# delta-bob-cat.net
KiCad netlist of a schematic drawn in Altium Designer
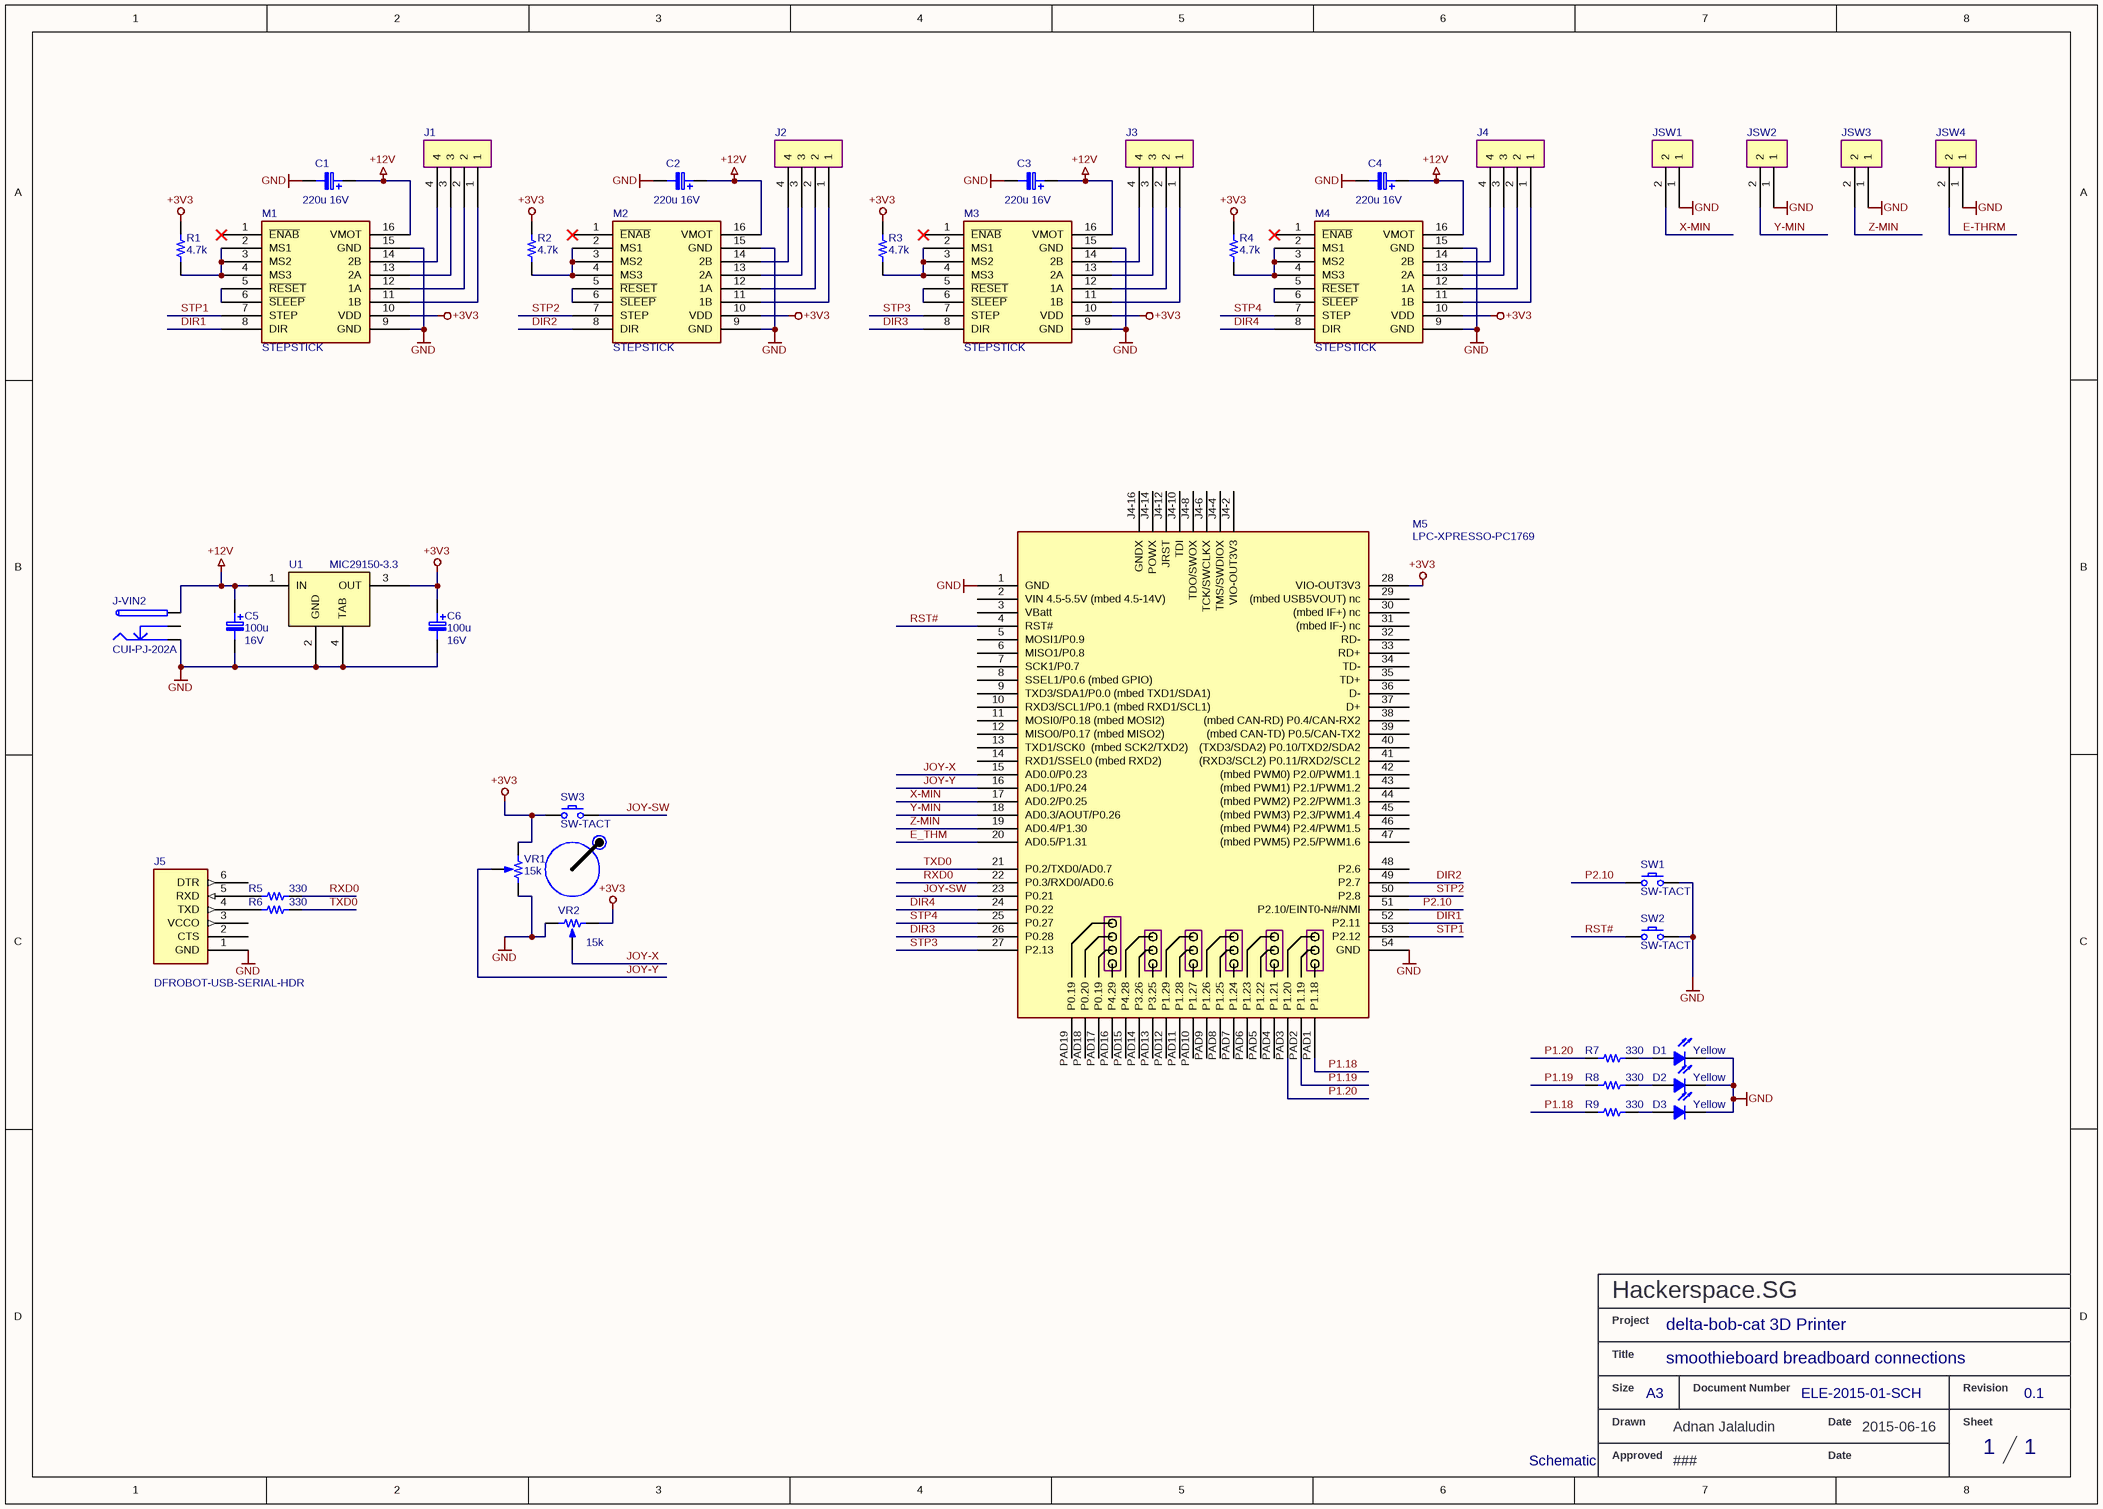
[diagram p0: delta-bob-cat.SchDoc]

(export (version "E")
  (design (tool "Eeschema 10.0.6"))
  (components
    (comp (ref "C1")
      (value "220u")
      (footprint "ECAP-D")
      (description "Cap Elect SMT Dia 6.3mm")
      (fields (field (name "TOLERANCE") "20%") (field (name "RATING") "16V"))
      (libsource (lib "AjDiscrete") (part "CElect"))
    )
    (comp (ref "C2")
      (value "220u")
      (footprint "ECAP-D")
      (description "Cap Elect SMT Dia 6.3mm")
      (fields (field (name "TOLERANCE") "20%") (field (name "RATING") "16V"))
      (libsource (lib "AjDiscrete") (part "CElect"))
    )
    (comp (ref "C3")
      (value "220u")
      (footprint "ECAP-D")
      (description "Cap Elect SMT Dia 6.3mm")
      (fields (field (name "TOLERANCE") "20%") (field (name "RATING") "16V"))
      (libsource (lib "AjDiscrete") (part "CElect"))
    )
    (comp (ref "C4")
      (value "220u")
      (footprint "ECAP-D")
      (description "Cap Elect SMT Dia 6.3mm")
      (fields (field (name "TOLERANCE") "20%") (field (name "RATING") "16V"))
      (libsource (lib "AjDiscrete") (part "CElect"))
    )
    (comp (ref "C5")
      (value "100u")
      (footprint "ECAP-A")
      (description "Cap Elect")
      (fields (field (name "TOLERANCE") "20%") (field (name "RATING") "16V"))
      (libsource (lib "AjDiscrete") (part "CElect"))
    )
    (comp (ref "C6")
      (value "100u")
      (footprint "ECAP-A")
      (description "Cap Elect")
      (fields (field (name "TOLERANCE") "20%") (field (name "RATING") "16V"))
      (libsource (lib "AjDiscrete") (part "CElect"))
    )
    (comp (ref "D1")
      (value "Yellow")
      (footprint "RC0603P")
      (description "LED")
      (libsource (lib "AjDiscrete") (part "LED_OLD"))
    )
    (comp (ref "D2")
      (value "Yellow")
      (footprint "RC0603P")
      (description "LED")
      (libsource (lib "AjDiscrete") (part "LED_OLD"))
    )
    (comp (ref "D3")
      (value "Yellow")
      (footprint "RC0603P")
      (description "LED")
      (libsource (lib "AjDiscrete") (part "LED_OLD"))
    )
    (comp (ref "J-VIN2")
      (value "CUI-PJ-202A")
      (footprint "POWER-CUI-PJ-202A")
      (description "Jack Power 2.10/6.50mm")
      (libsource (lib "AjConn") (part "POWER-SKT-LV"))
    )
    (comp (ref "J1")
      (value "HDR-4")
      (footprint "HDR4-P2.50-VSTRIP")
      (description "Header, 4-pin")
      (libsource (lib "AjConn") (part "HDR-4"))
    )
    (comp (ref "J2")
      (value "HDR-4")
      (footprint "HDR4-P2.50-VSTRIP")
      (description "Header, 4-pin")
      (libsource (lib "AjConn") (part "HDR-4"))
    )
    (comp (ref "J3")
      (value "HDR-4")
      (footprint "HDR4-P2.50-VSTRIP")
      (description "Header, 4-pin")
      (libsource (lib "AjConn") (part "HDR-4"))
    )
    (comp (ref "J4")
      (value "HDR-4")
      (footprint "HDR4-P2.50-VSTRIP")
      (description "Header, 4-pin")
      (libsource (lib "AjConn") (part "HDR-4"))
    )
    (comp (ref "J5")
      (value "DFROBOT-USB-SERIAL-HDR")
      (footprint "HDR6-P2.50-VSTRIP")
      (description "Module, Bluetooth")
      (libsource (lib "AjModule") (part "DFROBOT-USB-SERIAL-HDR"))
    )
    (comp (ref "JSW1")
      (value "HDR-2")
      (footprint "HDR2-P2.50-VSTRIP")
      (description "Header, 2-pin")
      (libsource (lib "AjConn") (part "HDR-2"))
    )
    (comp (ref "JSW2")
      (value "HDR-2")
      (footprint "HDR2-P2.50-VSTRIP")
      (description "Header, 2-pin")
      (libsource (lib "AjConn") (part "HDR-2"))
    )
    (comp (ref "JSW3")
      (value "HDR-2")
      (footprint "HDR2-P2.50-VSTRIP")
      (description "Header, 2-pin")
      (libsource (lib "AjConn") (part "HDR-2"))
    )
    (comp (ref "JSW4")
      (value "HDR-2")
      (footprint "HDR2-P2.50-VSTRIP")
      (description "Header, 2-pin")
      (libsource (lib "AjConn") (part "HDR-2"))
    )
    (comp (ref "M1")
      (value "STEPSTICK")
      (footprint "MODULE-STEPSTICK")
      (description "Module Stepstick")
      (libsource (lib "AjModule") (part "STEPSTICK"))
    )
    (comp (ref "M2")
      (value "STEPSTICK")
      (footprint "MODULE-STEPSTICK")
      (description "Module Stepstick")
      (libsource (lib "AjModule") (part "STEPSTICK"))
    )
    (comp (ref "M3")
      (value "STEPSTICK")
      (footprint "MODULE-STEPSTICK")
      (description "Module Stepstick")
      (libsource (lib "AjModule") (part "STEPSTICK"))
    )
    (comp (ref "M4")
      (value "STEPSTICK")
      (footprint "MODULE-STEPSTICK")
      (description "Module Stepstick")
      (libsource (lib "AjModule") (part "STEPSTICK"))
    )
    (comp (ref "M5")
      (value "LPC-XPRESSO-PC1769")
      (footprint "MODULE-MBED-XPRESSO-EXTND")
      (description "Module LPC-Xpresso-PC1769")
      (libsource (lib "AjModule") (part "LPC-XPRESSO-PC1769"))
    )
    (comp (ref "R1")
      (value "4.7k")
      (footprint "RC0603")
      (description "Res Chip")
      (fields (field (name "TOLERANCE") "5%"))
      (libsource (lib "AjDiscrete") (part "R"))
    )
    (comp (ref "R2")
      (value "4.7k")
      (footprint "RC0603")
      (description "Res Chip")
      (fields (field (name "TOLERANCE") "5%"))
      (libsource (lib "AjDiscrete") (part "R"))
    )
    (comp (ref "R3")
      (value "4.7k")
      (footprint "RC0603")
      (description "Res Chip")
      (fields (field (name "TOLERANCE") "5%"))
      (libsource (lib "AjDiscrete") (part "R"))
    )
    (comp (ref "R4")
      (value "4.7k")
      (footprint "RC0603")
      (description "Res Chip")
      (fields (field (name "TOLERANCE") "5%"))
      (libsource (lib "AjDiscrete") (part "R"))
    )
    (comp (ref "R5")
      (value "330")
      (footprint "RC0603")
      (description "Res Chip")
      (fields (field (name "TOLERANCE") "5%"))
      (libsource (lib "AjDiscrete") (part "R"))
    )
    (comp (ref "R6")
      (value "330")
      (footprint "RC0603")
      (description "Res Chip")
      (fields (field (name "TOLERANCE") "5%"))
      (libsource (lib "AjDiscrete") (part "R"))
    )
    (comp (ref "R7")
      (value "330")
      (footprint "RC0603")
      (description "Res Chip")
      (fields (field (name "TOLERANCE") "5%"))
      (libsource (lib "AjDiscrete") (part "R"))
    )
    (comp (ref "R8")
      (value "330")
      (footprint "RC0603")
      (description "Res Chip")
      (fields (field (name "TOLERANCE") "5%"))
      (libsource (lib "AjDiscrete") (part "R"))
    )
    (comp (ref "R9")
      (value "330")
      (footprint "RC0603")
      (description "Res Chip")
      (fields (field (name "TOLERANCE") "5%"))
      (libsource (lib "AjDiscrete") (part "R"))
    )
    (comp (ref "SW1")
      (value "SW-TACT")
      (footprint "SWTACT2-P6.50-W3.50")
      (description "Switch SPST-NO Tactile")
      (libsource (lib "AjDiscrete") (part "SW-TACT"))
    )
    (comp (ref "SW2")
      (value "SW-TACT")
      (footprint "SWTACT2-P6.50-W3.50")
      (description "Switch SPST-NO Tactile")
      (libsource (lib "AjDiscrete") (part "SW-TACT"))
    )
    (comp (ref "SW3")
      (value "SW-TACT")
      (footprint "SWTACT2-P6.50-W3.50")
      (description "Switch SPST-NO Tactile")
      (libsource (lib "AjDiscrete") (part "SW-TACT"))
    )
    (comp (ref "U1")
      (value "MIC29150-3.3")
      (footprint "TO263")
      (description "IC Regulator LDO")
      (libsource (lib "AjPower") (part "MIC29150"))
    )
    (comp (ref "VR1")
      (value "15k")
      (footprint "BI-TRIMMER68W")
      (description "Res Trimmer")
      (libsource (lib "AjDiscrete") (part "POT"))
    )
    (comp (ref "VR2")
      (value "15k")
      (footprint "BI-TRIMMER68W")
      (description "Res Trimmer")
      (libsource (lib "AjDiscrete") (part "POT"))
    )
  )
  (nets
    (net (code "1") (name "+3V3") (class "Default")
      (node (ref "C6") (pin "1") (pinfunction "1_1") (pintype "passive"))
      (node (ref "M1") (pin "10") (pinfunction "VDD_10") (pintype "passive"))
      (node (ref "M2") (pin "10") (pinfunction "VDD_10") (pintype "passive"))
      (node (ref "M3") (pin "10") (pinfunction "VDD_10") (pintype "passive"))
      (node (ref "M4") (pin "10") (pinfunction "VDD_10") (pintype "passive"))
      (node (ref "M5") (pin "28") (pinfunction "VIO-OUT3V3_28") (pintype "passive"))
      (node (ref "R1") (pin "2") (pinfunction "BOT_2") (pintype "passive"))
      (node (ref "R2") (pin "2") (pinfunction "BOT_2") (pintype "passive"))
      (node (ref "R3") (pin "2") (pinfunction "BOT_2") (pintype "passive"))
      (node (ref "R4") (pin "2") (pinfunction "BOT_2") (pintype "passive"))
      (node (ref "SW3") (pin "1") (pinfunction "1_1") (pintype "passive"))
      (node (ref "U1") (pin "3") (pinfunction "OUT_3") (pintype "passive"))
      (node (ref "VR1") (pin "1") (pinfunction "CCW_1") (pintype "passive"))
      (node (ref "VR2") (pin "3") (pinfunction "CW_3") (pintype "passive"))
    )
    (net (code "2") (name "+12V") (class "Default")
      (node (ref "C1") (pin "1") (pinfunction "1_1") (pintype "passive"))
      (node (ref "C2") (pin "1") (pinfunction "1_1") (pintype "passive"))
      (node (ref "C3") (pin "1") (pinfunction "1_1") (pintype "passive"))
      (node (ref "C4") (pin "1") (pinfunction "1_1") (pintype "passive"))
      (node (ref "C5") (pin "1") (pinfunction "1_1") (pintype "passive"))
      (node (ref "J-VIN2") (pin "1") (pinfunction "1_1") (pintype "power_in"))
      (node (ref "M1") (pin "16") (pinfunction "VMOT_16") (pintype "passive"))
      (node (ref "M2") (pin "16") (pinfunction "VMOT_16") (pintype "passive"))
      (node (ref "M3") (pin "16") (pinfunction "VMOT_16") (pintype "passive"))
      (node (ref "M4") (pin "16") (pinfunction "VMOT_16") (pintype "passive"))
      (node (ref "U1") (pin "1") (pinfunction "IN_1") (pintype "passive"))
    )
    (net (code "3") (name "/DIR1") (class "Default")
      (node (ref "M1") (pin "8") (pinfunction "DIR_8") (pintype "passive"))
      (node (ref "M5") (pin "52") (pinfunction "P2.11_52") (pintype "passive"))
    )
    (net (code "4") (name "/DIR2") (class "Default")
      (node (ref "M2") (pin "8") (pinfunction "DIR_8") (pintype "passive"))
      (node (ref "M5") (pin "49") (pinfunction "P2.7_49") (pintype "passive"))
    )
    (net (code "5") (name "/DIR3") (class "Default")
      (node (ref "M3") (pin "8") (pinfunction "DIR_8") (pintype "passive"))
      (node (ref "M5") (pin "26") (pinfunction "P0.28_26") (pintype "passive"))
    )
    (net (code "6") (name "/DIR4") (class "Default")
      (node (ref "M4") (pin "8") (pinfunction "DIR_8") (pintype "passive"))
      (node (ref "M5") (pin "24") (pinfunction "P0.22_24") (pintype "passive"))
    )
    (net (code "7") (name "/E-THRM") (class "Default")
      (node (ref "JSW4") (pin "2") (pinfunction "2_2") (pintype "passive"))
    )
    (net (code "8") (name "/E_THM") (class "Default")
      (node (ref "M5") (pin "20") (pinfunction "AD0.5/P1.31_20") (pintype "passive"))
    )
    (net (code "9") (name "/JOY-SW") (class "Default")
      (node (ref "M5") (pin "23") (pinfunction "P0.21_23") (pintype "passive"))
      (node (ref "SW3") (pin "2") (pinfunction "2_2") (pintype "passive"))
    )
    (net (code "10") (name "/JOY-X") (class "Default")
      (node (ref "M5") (pin "15") (pinfunction "AD0.0/P0.23_15") (pintype "passive"))
      (node (ref "VR2") (pin "2") (pinfunction "TAP_2") (pintype "passive"))
    )
    (net (code "11") (name "/JOY-Y") (class "Default")
      (node (ref "M5") (pin "16") (pinfunction "AD0.1/P0.24_16") (pintype "passive"))
      (node (ref "VR1") (pin "2") (pinfunction "TAP_2") (pintype "passive"))
    )
    (net (code "12") (name "/P1.18") (class "Default")
      (node (ref "M5") (pin "PAD1") (pinfunction "P1.18_PAD1") (pintype "passive"))
      (node (ref "R9") (pin "1") (pinfunction "TOP_1") (pintype "passive"))
    )
    (net (code "13") (name "/P1.19") (class "Default")
      (node (ref "M5") (pin "PAD2") (pinfunction "P1.19_PAD2") (pintype "passive"))
      (node (ref "R8") (pin "1") (pinfunction "TOP_1") (pintype "passive"))
    )
    (net (code "14") (name "/P1.20") (class "Default")
      (node (ref "M5") (pin "PAD3") (pinfunction "P1.20_PAD3") (pintype "passive"))
      (node (ref "R7") (pin "1") (pinfunction "TOP_1") (pintype "passive"))
    )
    (net (code "15") (name "/P2.10") (class "Default")
      (node (ref "M5") (pin "51") (pinfunction "P2.10/EINT0-N#/NMI_51") (pintype "passive"))
      (node (ref "SW1") (pin "2") (pinfunction "2_2") (pintype "passive"))
    )
    (net (code "16") (name "/RST#") (class "Default")
      (node (ref "M5") (pin "4") (pinfunction "RST#_4") (pintype "passive"))
      (node (ref "SW2") (pin "2") (pinfunction "2_2") (pintype "passive"))
    )
    (net (code "17") (name "/RXD0") (class "Default")
      (node (ref "M5") (pin "22") (pinfunction "P0.3/RXD0/AD0.6_22") (pintype "passive"))
      (node (ref "R5") (pin "2") (pinfunction "BOT_2") (pintype "passive"))
    )
    (net (code "18") (name "/STP1") (class "Default")
      (node (ref "M1") (pin "7") (pinfunction "STEP_7") (pintype "passive"))
      (node (ref "M5") (pin "53") (pinfunction "P2.12_53") (pintype "passive"))
    )
    (net (code "19") (name "/STP2") (class "Default")
      (node (ref "M2") (pin "7") (pinfunction "STEP_7") (pintype "passive"))
      (node (ref "M5") (pin "50") (pinfunction "P2.8_50") (pintype "passive"))
    )
    (net (code "20") (name "/STP3") (class "Default")
      (node (ref "M3") (pin "7") (pinfunction "STEP_7") (pintype "passive"))
      (node (ref "M5") (pin "27") (pinfunction "P2.13_27") (pintype "passive"))
    )
    (net (code "21") (name "/STP4") (class "Default")
      (node (ref "M4") (pin "7") (pinfunction "STEP_7") (pintype "passive"))
      (node (ref "M5") (pin "25") (pinfunction "P0.27_25") (pintype "passive"))
    )
    (net (code "22") (name "/TXD0") (class "Default")
      (node (ref "M5") (pin "21") (pinfunction "P0.2/TXD0/AD0.7_21") (pintype "passive"))
      (node (ref "R6") (pin "2") (pinfunction "BOT_2") (pintype "passive"))
    )
    (net (code "23") (name "/X-MIN") (class "Default")
      (node (ref "JSW1") (pin "2") (pinfunction "2_2") (pintype "passive"))
      (node (ref "M5") (pin "17") (pinfunction "AD0.2/P0.25_17") (pintype "passive"))
    )
    (net (code "24") (name "/Y-MIN") (class "Default")
      (node (ref "JSW2") (pin "2") (pinfunction "2_2") (pintype "passive"))
      (node (ref "M5") (pin "18") (pinfunction "AD0.3/AOUT/P0.26_18") (pintype "passive"))
    )
    (net (code "25") (name "/Z-MIN") (class "Default")
      (node (ref "JSW3") (pin "2") (pinfunction "2_2") (pintype "passive"))
      (node (ref "M5") (pin "19") (pinfunction "AD0.4/P1.30_19") (pintype "passive"))
    )
    (net (code "26") (name "GND") (class "Default")
      (node (ref "C1") (pin "2") (pinfunction "2_2") (pintype "passive"))
      (node (ref "C2") (pin "2") (pinfunction "2_2") (pintype "passive"))
      (node (ref "C3") (pin "2") (pinfunction "2_2") (pintype "passive"))
      (node (ref "C4") (pin "2") (pinfunction "2_2") (pintype "passive"))
      (node (ref "C5") (pin "2") (pinfunction "2_2") (pintype "passive"))
      (node (ref "C6") (pin "2") (pinfunction "2_2") (pintype "passive"))
      (node (ref "D1") (pin "1") (pinfunction "K_1") (pintype "passive"))
      (node (ref "D2") (pin "1") (pinfunction "K_1") (pintype "passive"))
      (node (ref "D3") (pin "1") (pinfunction "K_1") (pintype "passive"))
      (node (ref "J-VIN2") (pin "2") (pinfunction "2_2") (pintype "power_in"))
      (node (ref "J5") (pin "1") (pinfunction "GND_1") (pintype "passive"))
      (node (ref "JSW1") (pin "1") (pinfunction "1_1") (pintype "passive"))
      (node (ref "JSW2") (pin "1") (pinfunction "1_1") (pintype "passive"))
      (node (ref "JSW3") (pin "1") (pinfunction "1_1") (pintype "passive"))
      (node (ref "JSW4") (pin "1") (pinfunction "1_1") (pintype "passive"))
      (node (ref "M1") (pin "15") (pinfunction "GND_15") (pintype "passive"))
      (node (ref "M1") (pin "9") (pinfunction "GND_9") (pintype "passive"))
      (node (ref "M2") (pin "15") (pinfunction "GND_15") (pintype "passive"))
      (node (ref "M2") (pin "9") (pinfunction "GND_9") (pintype "passive"))
      (node (ref "M3") (pin "15") (pinfunction "GND_15") (pintype "passive"))
      (node (ref "M3") (pin "9") (pinfunction "GND_9") (pintype "passive"))
      (node (ref "M4") (pin "15") (pinfunction "GND_15") (pintype "passive"))
      (node (ref "M4") (pin "9") (pinfunction "GND_9") (pintype "passive"))
      (node (ref "M5") (pin "1") (pinfunction "GND_1") (pintype "passive"))
      (node (ref "M5") (pin "54") (pinfunction "GND_54") (pintype "passive"))
      (node (ref "SW1") (pin "1") (pinfunction "1_1") (pintype "passive"))
      (node (ref "SW2") (pin "1") (pinfunction "1_1") (pintype "passive"))
      (node (ref "U1") (pin "2") (pinfunction "GND_2") (pintype "passive"))
      (node (ref "U1") (pin "4") (pinfunction "TAB_4") (pintype "passive"))
      (node (ref "VR1") (pin "3") (pinfunction "CW_3") (pintype "passive"))
      (node (ref "VR2") (pin "1") (pinfunction "CCW_1") (pintype "passive"))
    )
    (net (code "27") (name "Net-(D1-A)") (class "Default")
      (node (ref "D1") (pin "2") (pinfunction "A_2") (pintype "passive"))
      (node (ref "R7") (pin "2") (pinfunction "BOT_2") (pintype "passive"))
    )
    (net (code "28") (name "Net-(D2-A)") (class "Default")
      (node (ref "D2") (pin "2") (pinfunction "A_2") (pintype "passive"))
      (node (ref "R8") (pin "2") (pinfunction "BOT_2") (pintype "passive"))
    )
    (net (code "29") (name "Net-(D3-A)") (class "Default")
      (node (ref "D3") (pin "2") (pinfunction "A_2") (pintype "passive"))
      (node (ref "R9") (pin "2") (pinfunction "BOT_2") (pintype "passive"))
    )
    (net (code "30") (name "Net-(J5-RXD)") (class "Default")
      (node (ref "J5") (pin "5") (pinfunction "RXD_5") (pintype "input"))
      (node (ref "R5") (pin "1") (pinfunction "TOP_1") (pintype "passive"))
    )
    (net (code "31") (name "Net-(J5-TXD)") (class "Default")
      (node (ref "J5") (pin "4") (pinfunction "TXD_4") (pintype "output"))
      (node (ref "R6") (pin "1") (pinfunction "TOP_1") (pintype "passive"))
    )
    (net (code "32") (name "Net-(M1-1A)") (class "Default")
      (node (ref "J1") (pin "2") (pinfunction "2_2") (pintype "passive"))
      (node (ref "M1") (pin "12") (pinfunction "1A_12") (pintype "passive"))
    )
    (net (code "33") (name "Net-(M1-1B)") (class "Default")
      (node (ref "J1") (pin "1") (pinfunction "1_1") (pintype "passive"))
      (node (ref "M1") (pin "11") (pinfunction "1B_11") (pintype "passive"))
    )
    (net (code "34") (name "Net-(M1-2A)") (class "Default")
      (node (ref "J1") (pin "3") (pinfunction "3_3") (pintype "passive"))
      (node (ref "M1") (pin "13") (pinfunction "2A_13") (pintype "passive"))
    )
    (net (code "35") (name "Net-(M1-2B)") (class "Default")
      (node (ref "J1") (pin "4") (pinfunction "4_4") (pintype "passive"))
      (node (ref "M1") (pin "14") (pinfunction "2B_14") (pintype "passive"))
    )
    (net (code "36") (name "Net-(M1-MS1)") (class "Default")
      (node (ref "M1") (pin "2") (pinfunction "MS1_2") (pintype "passive"))
      (node (ref "M1") (pin "3") (pinfunction "MS2_3") (pintype "passive"))
      (node (ref "M1") (pin "4") (pinfunction "MS3_4") (pintype "passive"))
      (node (ref "R1") (pin "1") (pinfunction "TOP_1") (pintype "passive"))
    )
    (net (code "37") (name "Net-(M1-~{RESET})") (class "Default")
      (node (ref "M1") (pin "5") (pinfunction "~{RESET}_5") (pintype "passive"))
      (node (ref "M1") (pin "6") (pinfunction "~{SLEEP}_6") (pintype "passive"))
    )
    (net (code "38") (name "Net-(M2-1A)") (class "Default")
      (node (ref "J2") (pin "2") (pinfunction "2_2") (pintype "passive"))
      (node (ref "M2") (pin "12") (pinfunction "1A_12") (pintype "passive"))
    )
    (net (code "39") (name "Net-(M2-1B)") (class "Default")
      (node (ref "J2") (pin "1") (pinfunction "1_1") (pintype "passive"))
      (node (ref "M2") (pin "11") (pinfunction "1B_11") (pintype "passive"))
    )
    (net (code "40") (name "Net-(M2-2A)") (class "Default")
      (node (ref "J2") (pin "3") (pinfunction "3_3") (pintype "passive"))
      (node (ref "M2") (pin "13") (pinfunction "2A_13") (pintype "passive"))
    )
    (net (code "41") (name "Net-(M2-2B)") (class "Default")
      (node (ref "J2") (pin "4") (pinfunction "4_4") (pintype "passive"))
      (node (ref "M2") (pin "14") (pinfunction "2B_14") (pintype "passive"))
    )
    (net (code "42") (name "Net-(M2-MS1)") (class "Default")
      (node (ref "M2") (pin "2") (pinfunction "MS1_2") (pintype "passive"))
      (node (ref "M2") (pin "3") (pinfunction "MS2_3") (pintype "passive"))
      (node (ref "M2") (pin "4") (pinfunction "MS3_4") (pintype "passive"))
      (node (ref "R2") (pin "1") (pinfunction "TOP_1") (pintype "passive"))
    )
    (net (code "43") (name "Net-(M2-~{RESET})") (class "Default")
      (node (ref "M2") (pin "5") (pinfunction "~{RESET}_5") (pintype "passive"))
      (node (ref "M2") (pin "6") (pinfunction "~{SLEEP}_6") (pintype "passive"))
    )
    (net (code "44") (name "Net-(M3-1A)") (class "Default")
      (node (ref "J3") (pin "2") (pinfunction "2_2") (pintype "passive"))
      (node (ref "M3") (pin "12") (pinfunction "1A_12") (pintype "passive"))
    )
    (net (code "45") (name "Net-(M3-1B)") (class "Default")
      (node (ref "J3") (pin "1") (pinfunction "1_1") (pintype "passive"))
      (node (ref "M3") (pin "11") (pinfunction "1B_11") (pintype "passive"))
    )
    (net (code "46") (name "Net-(M3-2A)") (class "Default")
      (node (ref "J3") (pin "3") (pinfunction "3_3") (pintype "passive"))
      (node (ref "M3") (pin "13") (pinfunction "2A_13") (pintype "passive"))
    )
    (net (code "47") (name "Net-(M3-2B)") (class "Default")
      (node (ref "J3") (pin "4") (pinfunction "4_4") (pintype "passive"))
      (node (ref "M3") (pin "14") (pinfunction "2B_14") (pintype "passive"))
    )
    (net (code "48") (name "Net-(M3-MS1)") (class "Default")
      (node (ref "M3") (pin "2") (pinfunction "MS1_2") (pintype "passive"))
      (node (ref "M3") (pin "3") (pinfunction "MS2_3") (pintype "passive"))
      (node (ref "M3") (pin "4") (pinfunction "MS3_4") (pintype "passive"))
      (node (ref "R3") (pin "1") (pinfunction "TOP_1") (pintype "passive"))
    )
    (net (code "49") (name "Net-(M3-~{RESET})") (class "Default")
      (node (ref "M3") (pin "5") (pinfunction "~{RESET}_5") (pintype "passive"))
      (node (ref "M3") (pin "6") (pinfunction "~{SLEEP}_6") (pintype "passive"))
    )
    (net (code "50") (name "Net-(M4-1A)") (class "Default")
      (node (ref "J4") (pin "2") (pinfunction "2_2") (pintype "passive"))
      (node (ref "M4") (pin "12") (pinfunction "1A_12") (pintype "passive"))
    )
    (net (code "51") (name "Net-(M4-1B)") (class "Default")
      (node (ref "J4") (pin "1") (pinfunction "1_1") (pintype "passive"))
      (node (ref "M4") (pin "11") (pinfunction "1B_11") (pintype "passive"))
    )
    (net (code "52") (name "Net-(M4-2A)") (class "Default")
      (node (ref "J4") (pin "3") (pinfunction "3_3") (pintype "passive"))
      (node (ref "M4") (pin "13") (pinfunction "2A_13") (pintype "passive"))
    )
    (net (code "53") (name "Net-(M4-2B)") (class "Default")
      (node (ref "J4") (pin "4") (pinfunction "4_4") (pintype "passive"))
      (node (ref "M4") (pin "14") (pinfunction "2B_14") (pintype "passive"))
    )
    (net (code "54") (name "Net-(M4-MS1)") (class "Default")
      (node (ref "M4") (pin "2") (pinfunction "MS1_2") (pintype "passive"))
      (node (ref "M4") (pin "3") (pinfunction "MS2_3") (pintype "passive"))
      (node (ref "M4") (pin "4") (pinfunction "MS3_4") (pintype "passive"))
      (node (ref "R4") (pin "1") (pinfunction "TOP_1") (pintype "passive"))
    )
    (net (code "55") (name "Net-(M4-~{RESET})") (class "Default")
      (node (ref "M4") (pin "5") (pinfunction "~{RESET}_5") (pintype "passive"))
      (node (ref "M4") (pin "6") (pinfunction "~{SLEEP}_6") (pintype "passive"))
    )
    (net (code "56") (name "unconnected-(J-VIN2-Pad3)") (class "Default")
      (node (ref "J-VIN2") (pin "3") (pinfunction "3_3") (pintype "power_in"))
    )
    (net (code "57") (name "unconnected-(J5-CTS-Pad2)") (class "Default")
      (node (ref "J5") (pin "2") (pinfunction "CTS_2") (pintype "passive"))
    )
    (net (code "58") (name "unconnected-(J5-DTR-Pad6)") (class "Default")
      (node (ref "J5") (pin "6") (pinfunction "DTR_6") (pintype "output"))
    )
    (net (code "59") (name "unconnected-(J5-VCCO-Pad3)") (class "Default")
      (node (ref "J5") (pin "3") (pinfunction "VCCO_3") (pintype "output"))
    )
    (net (code "60") (name "unconnected-(M1-~{ENAB}-Pad1)") (class "Default")
      (node (ref "M1") (pin "1") (pinfunction "~{ENAB}_1") (pintype "passive+no_connect"))
    )
    (net (code "61") (name "unconnected-(M2-~{ENAB}-Pad1)") (class "Default")
      (node (ref "M2") (pin "1") (pinfunction "~{ENAB}_1") (pintype "passive+no_connect"))
    )
    (net (code "62") (name "unconnected-(M3-~{ENAB}-Pad1)") (class "Default")
      (node (ref "M3") (pin "1") (pinfunction "~{ENAB}_1") (pintype "passive+no_connect"))
    )
    (net (code "63") (name "unconnected-(M4-~{ENAB}-Pad1)") (class "Default")
      (node (ref "M4") (pin "1") (pinfunction "~{ENAB}_1") (pintype "passive+no_connect"))
    )
    (net (code "64") (name "unconnected-(M5-(RXD3{slash}SCL2)_P0.11{slash}RXD2{slash}SCL2-Pad41)") (class "Default")
      (node (ref "M5") (pin "41") (pinfunction "(RXD3/SCL2)_P0.11/RXD2/SCL2_41") (pintype "passive"))
    )
    (net (code "65") (name "unconnected-(M5-(TXD3{slash}SDA2)_P0.10{slash}TXD2{slash}SDA2-Pad40)") (class "Default")
      (node (ref "M5") (pin "40") (pinfunction "(TXD3/SDA2)_P0.10/TXD2/SDA2_40") (pintype "passive"))
    )
    (net (code "66") (name "unconnected-(M5-(mbed_CAN-RD)_P0.4{slash}CAN-RX2-Pad38)") (class "Default")
      (node (ref "M5") (pin "38") (pinfunction "(mbed_CAN-RD)_P0.4/CAN-RX2_38") (pintype "passive"))
    )
    (net (code "67") (name "unconnected-(M5-(mbed_CAN-TD)_P0.5{slash}CAN-TX2-Pad39)") (class "Default")
      (node (ref "M5") (pin "39") (pinfunction "(mbed_CAN-TD)_P0.5/CAN-TX2_39") (pintype "passive"))
    )
    (net (code "68") (name "unconnected-(M5-(mbed_IF+)_nc-Pad30)") (class "Default")
      (node (ref "M5") (pin "30") (pinfunction "(mbed_IF+)_nc_30") (pintype "passive"))
    )
    (net (code "69") (name "unconnected-(M5-(mbed_IF-)_nc-Pad31)") (class "Default")
      (node (ref "M5") (pin "31") (pinfunction "(mbed_IF-)_nc_31") (pintype "passive"))
    )
    (net (code "70") (name "unconnected-(M5-(mbed_PWM0)_P2.0{slash}PWM1.1-Pad42)") (class "Default")
      (node (ref "M5") (pin "42") (pinfunction "(mbed_PWM0)_P2.0/PWM1.1_42") (pintype "passive"))
    )
    (net (code "71") (name "unconnected-(M5-(mbed_PWM1)_P2.1{slash}PWM1.2-Pad43)") (class "Default")
      (node (ref "M5") (pin "43") (pinfunction "(mbed_PWM1)_P2.1/PWM1.2_43") (pintype "passive"))
    )
    (net (code "72") (name "unconnected-(M5-(mbed_PWM2)_P2.2{slash}PWM1.3-Pad44)") (class "Default")
      (node (ref "M5") (pin "44") (pinfunction "(mbed_PWM2)_P2.2/PWM1.3_44") (pintype "passive"))
    )
    (net (code "73") (name "unconnected-(M5-(mbed_PWM3)_P2.3{slash}PWM1.4-Pad45)") (class "Default")
      (node (ref "M5") (pin "45") (pinfunction "(mbed_PWM3)_P2.3/PWM1.4_45") (pintype "passive"))
    )
    (net (code "74") (name "unconnected-(M5-(mbed_PWM4)_P2.4{slash}PWM1.5-Pad46)") (class "Default")
      (node (ref "M5") (pin "46") (pinfunction "(mbed_PWM4)_P2.4/PWM1.5_46") (pintype "passive"))
    )
    (net (code "75") (name "unconnected-(M5-(mbed_PWM5)_P2.5{slash}PWM1.6-Pad47)") (class "Default")
      (node (ref "M5") (pin "47") (pinfunction "(mbed_PWM5)_P2.5/PWM1.6_47") (pintype "passive"))
    )
    (net (code "76") (name "unconnected-(M5-(mbed_USB5VOUT)_nc-Pad29)") (class "Default")
      (node (ref "M5") (pin "29") (pinfunction "(mbed_USB5VOUT)_nc_29") (pintype "passive"))
    )
    (net (code "77") (name "unconnected-(M5-D+-Pad37)") (class "Default")
      (node (ref "M5") (pin "37") (pinfunction "D+_37") (pintype "passive"))
    )
    (net (code "78") (name "unconnected-(M5-D--Pad36)") (class "Default")
      (node (ref "M5") (pin "36") (pinfunction "D-_36") (pintype "passive"))
    )
    (net (code "79") (name "unconnected-(M5-GNDX-PadJ4-16)") (class "Default")
      (node (ref "M5") (pin "J4-16") (pinfunction "GNDX_J4-16") (pintype "passive"))
    )
    (net (code "80") (name "unconnected-(M5-JRST-PadJ4-12)") (class "Default")
      (node (ref "M5") (pin "J4-12") (pinfunction "JRST_J4-12") (pintype "passive"))
    )
    (net (code "81") (name "unconnected-(M5-MISO0{slash}P0.17_(mbed_MISO2)-Pad12)") (class "Default")
      (node (ref "M5") (pin "12") (pinfunction "MISO0/P0.17_(mbed_MISO2)_12") (pintype "passive"))
    )
    (net (code "82") (name "unconnected-(M5-MISO1{slash}P0.8-Pad6)") (class "Default")
      (node (ref "M5") (pin "6") (pinfunction "MISO1/P0.8_6") (pintype "passive"))
    )
    (net (code "83") (name "unconnected-(M5-MOSI0{slash}P0.18_(mbed_MOSI2)-Pad11)") (class "Default")
      (node (ref "M5") (pin "11") (pinfunction "MOSI0/P0.18_(mbed_MOSI2)_11") (pintype "passive"))
    )
    (net (code "84") (name "unconnected-(M5-MOSI1{slash}P0.9-Pad5)") (class "Default")
      (node (ref "M5") (pin "5") (pinfunction "MOSI1/P0.9_5") (pintype "passive"))
    )
    (net (code "85") (name "unconnected-(M5-P0.19-PadPAD17)") (class "Default")
      (node (ref "M5") (pin "PAD17") (pinfunction "P0.19_PAD17") (pintype "passive"))
    )
    (net (code "86") (name "unconnected-(M5-P0.19-PadPAD19)") (class "Default")
      (node (ref "M5") (pin "PAD19") (pinfunction "P0.19_PAD19") (pintype "passive"))
    )
    (net (code "87") (name "unconnected-(M5-P0.20-PadPAD18)") (class "Default")
      (node (ref "M5") (pin "PAD18") (pinfunction "P0.20_PAD18") (pintype "passive"))
    )
    (net (code "88") (name "unconnected-(M5-P1.21-PadPAD4)") (class "Default")
      (node (ref "M5") (pin "PAD4") (pinfunction "P1.21_PAD4") (pintype "passive"))
    )
    (net (code "89") (name "unconnected-(M5-P1.22-PadPAD5)") (class "Default")
      (node (ref "M5") (pin "PAD5") (pinfunction "P1.22_PAD5") (pintype "passive"))
    )
    (net (code "90") (name "unconnected-(M5-P1.23-PadPAD6)") (class "Default")
      (node (ref "M5") (pin "PAD6") (pinfunction "P1.23_PAD6") (pintype "passive"))
    )
    (net (code "91") (name "unconnected-(M5-P1.24-PadPAD7)") (class "Default")
      (node (ref "M5") (pin "PAD7") (pinfunction "P1.24_PAD7") (pintype "passive"))
    )
    (net (code "92") (name "unconnected-(M5-P1.25-PadPAD8)") (class "Default")
      (node (ref "M5") (pin "PAD8") (pinfunction "P1.25_PAD8") (pintype "passive"))
    )
    (net (code "93") (name "unconnected-(M5-P1.26-PadPAD9)") (class "Default")
      (node (ref "M5") (pin "PAD9") (pinfunction "P1.26_PAD9") (pintype "passive"))
    )
    (net (code "94") (name "unconnected-(M5-P1.27-PadPAD10)") (class "Default")
      (node (ref "M5") (pin "PAD10") (pinfunction "P1.27_PAD10") (pintype "passive"))
    )
    (net (code "95") (name "unconnected-(M5-P1.28-PadPAD11)") (class "Default")
      (node (ref "M5") (pin "PAD11") (pinfunction "P1.28_PAD11") (pintype "passive"))
    )
    (net (code "96") (name "unconnected-(M5-P1.29-PadPAD12)") (class "Default")
      (node (ref "M5") (pin "PAD12") (pinfunction "P1.29_PAD12") (pintype "passive"))
    )
    (net (code "97") (name "unconnected-(M5-P2.6-Pad48)") (class "Default")
      (node (ref "M5") (pin "48") (pinfunction "P2.6_48") (pintype "passive"))
    )
    (net (code "98") (name "unconnected-(M5-P3.25-PadPAD13)") (class "Default")
      (node (ref "M5") (pin "PAD13") (pinfunction "P3.25_PAD13") (pintype "passive"))
    )
    (net (code "99") (name "unconnected-(M5-P3.26-PadPAD14)") (class "Default")
      (node (ref "M5") (pin "PAD14") (pinfunction "P3.26_PAD14") (pintype "passive"))
    )
    (net (code "100") (name "unconnected-(M5-P4.28-PadPAD15)") (class "Default")
      (node (ref "M5") (pin "PAD15") (pinfunction "P4.28_PAD15") (pintype "passive"))
    )
    (net (code "101") (name "unconnected-(M5-P4.29-PadPAD16)") (class "Default")
      (node (ref "M5") (pin "PAD16") (pinfunction "P4.29_PAD16") (pintype "passive"))
    )
    (net (code "102") (name "unconnected-(M5-POWX-PadJ4-14)") (class "Default")
      (node (ref "M5") (pin "J4-14") (pinfunction "POWX_J4-14") (pintype "passive"))
    )
    (net (code "103") (name "unconnected-(M5-RD+-Pad33)") (class "Default")
      (node (ref "M5") (pin "33") (pinfunction "RD+_33") (pintype "passive"))
    )
    (net (code "104") (name "unconnected-(M5-RD--Pad32)") (class "Default")
      (node (ref "M5") (pin "32") (pinfunction "RD-_32") (pintype "passive"))
    )
    (net (code "105") (name "unconnected-(M5-RXD1{slash}SSEL0_(mbed_RXD2)-Pad14)") (class "Default")
      (node (ref "M5") (pin "14") (pinfunction "RXD1/SSEL0_(mbed_RXD2)_14") (pintype "passive"))
    )
    (net (code "106") (name "unconnected-(M5-RXD3{slash}SCL1{slash}P0.1_(mbed_RXD1{slash}SCL1)-Pad10)") (class "Default")
      (node (ref "M5") (pin "10") (pinfunction "RXD3/SCL1/P0.1_(mbed_RXD1/SCL1)_10") (pintype "passive"))
    )
    (net (code "107") (name "unconnected-(M5-SCK1{slash}P0.7-Pad7)") (class "Default")
      (node (ref "M5") (pin "7") (pinfunction "SCK1/P0.7_7") (pintype "passive"))
    )
    (net (code "108") (name "unconnected-(M5-SSEL1{slash}P0.6_(mbed_GPIO)-Pad8)") (class "Default")
      (node (ref "M5") (pin "8") (pinfunction "SSEL1/P0.6_(mbed_GPIO)_8") (pintype "passive"))
    )
    (net (code "109") (name "unconnected-(M5-TCK{slash}SWCLKX-PadJ4-6)") (class "Default")
      (node (ref "M5") (pin "J4-6") (pinfunction "TCK/SWCLKX_J4-6") (pintype "passive"))
    )
    (net (code "110") (name "unconnected-(M5-TD+-Pad35)") (class "Default")
      (node (ref "M5") (pin "35") (pinfunction "TD+_35") (pintype "passive"))
    )
    (net (code "111") (name "unconnected-(M5-TD--Pad34)") (class "Default")
      (node (ref "M5") (pin "34") (pinfunction "TD-_34") (pintype "passive"))
    )
    (net (code "112") (name "unconnected-(M5-TDI-PadJ4-10)") (class "Default")
      (node (ref "M5") (pin "J4-10") (pinfunction "TDI_J4-10") (pintype "passive"))
    )
    (net (code "113") (name "unconnected-(M5-TDO{slash}SWOX-PadJ4-8)") (class "Default")
      (node (ref "M5") (pin "J4-8") (pinfunction "TDO/SWOX_J4-8") (pintype "passive"))
    )
    (net (code "114") (name "unconnected-(M5-TMS{slash}SWDIOX-PadJ4-4)") (class "Default")
      (node (ref "M5") (pin "J4-4") (pinfunction "TMS/SWDIOX_J4-4") (pintype "passive"))
    )
    (net (code "115") (name "unconnected-(M5-TXD1{slash}SCK0__(mbed_SCK2{slash}TXD2)-Pad13)") (class "Default")
      (node (ref "M5") (pin "13") (pinfunction "TXD1/SCK0__(mbed_SCK2/TXD2)_13") (pintype "passive"))
    )
    (net (code "116") (name "unconnected-(M5-TXD3{slash}SDA1{slash}P0.0_(mbed_TXD1{slash}SDA1)-Pad9)") (class "Default")
      (node (ref "M5") (pin "9") (pinfunction "TXD3/SDA1/P0.0_(mbed_TXD1/SDA1)_9") (pintype "passive"))
    )
    (net (code "117") (name "unconnected-(M5-VBatt-Pad3)") (class "Default")
      (node (ref "M5") (pin "3") (pinfunction "VBatt_3") (pintype "passive"))
    )
    (net (code "118") (name "unconnected-(M5-VIN_4.5-5.5V_(mbed_4.5-14V)-Pad2)") (class "Default")
      (node (ref "M5") (pin "2") (pinfunction "VIN_4.5-5.5V_(mbed_4.5-14V)_2") (pintype "passive"))
    )
    (net (code "119") (name "unconnected-(M5-VIO-OUT3V3-PadJ4-2)") (class "Default")
      (node (ref "M5") (pin "J4-2") (pinfunction "VIO-OUT3V3_J4-2") (pintype "passive"))
    )
  )
)
